# Cheeta_Driver.net
KiCad netlist of a schematic drawn in Altium Designer
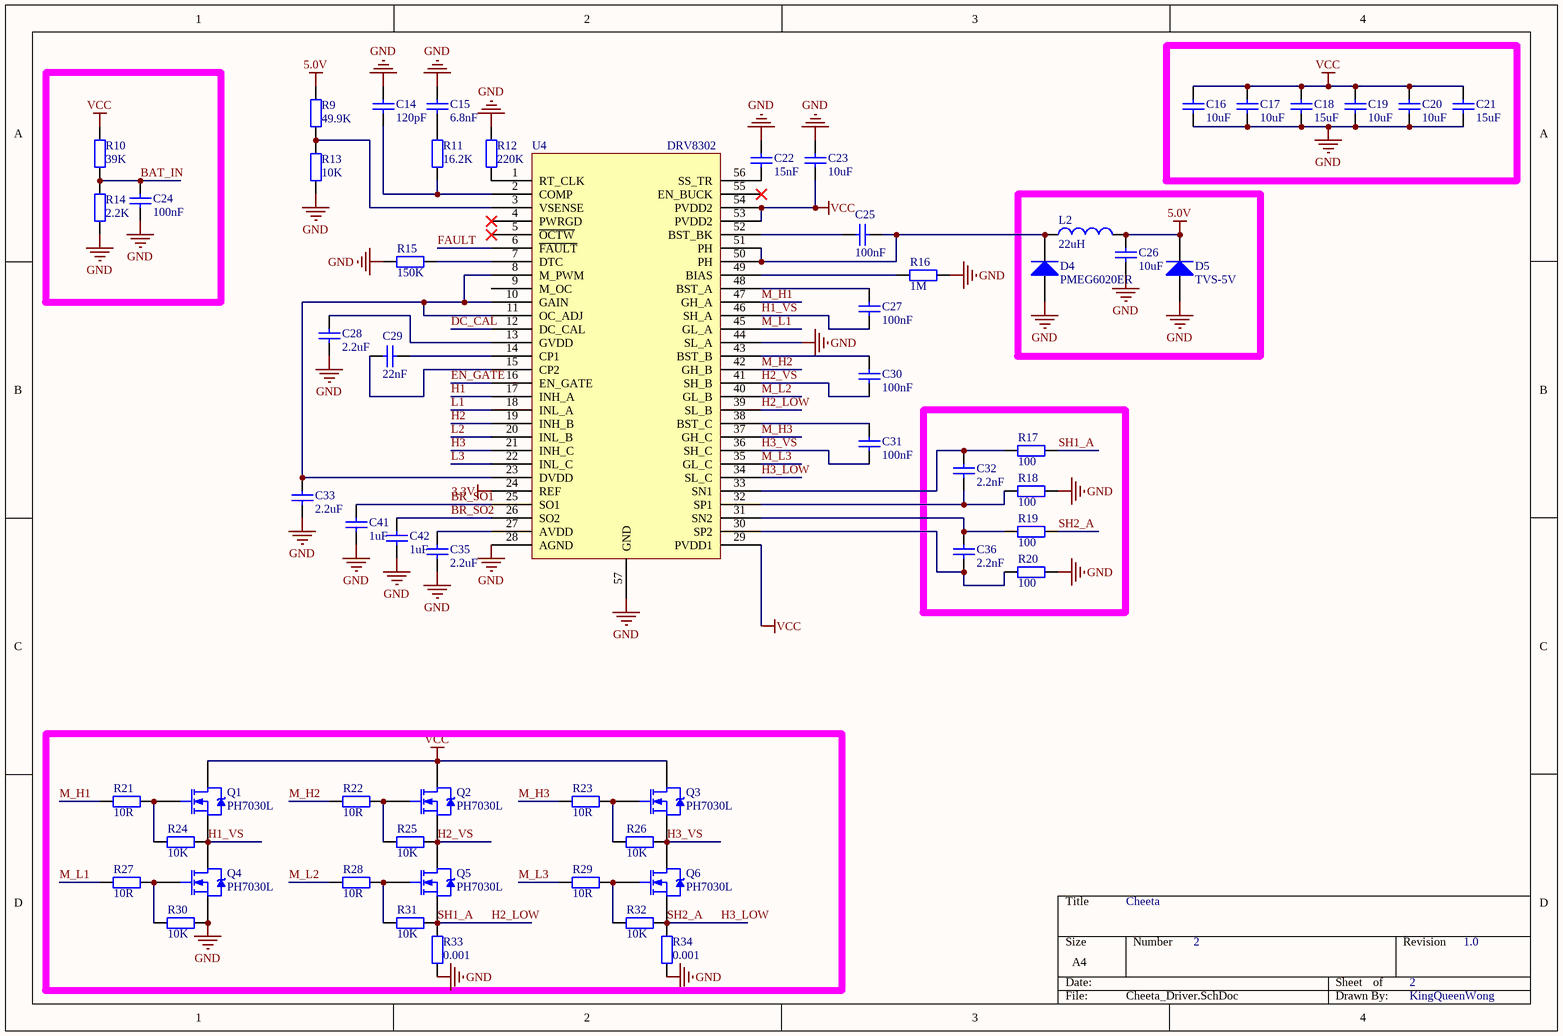
[diagram p0: Cheeta_Driver.SchDoc]

(export (version "E")
  (design (tool "Eeschema 10.0.6"))
  (components
    (comp (ref "C14")
      (value "120pF")
      (footprint "0603C")
      (description "Capacitor")
      (fields (field (name "Comment") "Cap") (field (name "PUBLISHER") "Altium Limited"))
      (libsource (lib "Miscellaneous Devices") (part "Cap"))
    )
    (comp (ref "C15")
      (value "6.8nF")
      (footprint "0603C")
      (description "Capacitor")
      (fields (field (name "Comment") "Cap") (field (name "PUBLISHER") "Altium Limited"))
      (libsource (lib "Miscellaneous Devices") (part "Cap"))
    )
    (comp (ref "C16")
      (value "10uF")
      (footprint "C1206")
      (description "Capacitor")
      (fields (field (name "Comment") "Cap") (field (name "PUBLISHER") "Altium Limited"))
      (libsource (lib "Miscellaneous Devices") (part "Cap"))
    )
    (comp (ref "C17")
      (value "10uF")
      (footprint "C1206")
      (description "Capacitor")
      (fields (field (name "Comment") "Cap") (field (name "PUBLISHER") "Altium Limited"))
      (libsource (lib "Miscellaneous Devices") (part "Cap"))
    )
    (comp (ref "C18")
      (value "15uF")
      (footprint "2220")
      (description "Capacitor")
      (fields (field (name "Comment") "Cap") (field (name "PUBLISHER") "Altium Limited"))
      (libsource (lib "Miscellaneous Devices") (part "Cap"))
    )
    (comp (ref "C19")
      (value "10uF")
      (footprint "C1206")
      (description "Capacitor")
      (fields (field (name "Comment") "Cap") (field (name "PUBLISHER") "Altium Limited"))
      (libsource (lib "Miscellaneous Devices") (part "Cap"))
    )
    (comp (ref "C20")
      (value "10uF")
      (footprint "C1206")
      (description "Capacitor")
      (fields (field (name "Comment") "Cap") (field (name "PUBLISHER") "Altium Limited"))
      (libsource (lib "Miscellaneous Devices") (part "Cap"))
    )
    (comp (ref "C21")
      (value "15uF")
      (footprint "2220")
      (description "Capacitor")
      (fields (field (name "Comment") "Cap") (field (name "PUBLISHER") "Altium Limited"))
      (libsource (lib "Miscellaneous Devices") (part "Cap"))
    )
    (comp (ref "C22")
      (value "15nF")
      (footprint "0603C")
      (description "Capacitor")
      (fields (field (name "Comment") "Cap") (field (name "PUBLISHER") "Altium Limited"))
      (libsource (lib "Miscellaneous Devices") (part "Cap"))
    )
    (comp (ref "C23")
      (value "10uF")
      (footprint "C1206")
      (description "Capacitor")
      (fields (field (name "Comment") "Cap") (field (name "PUBLISHER") "Altium Limited"))
      (libsource (lib "Miscellaneous Devices") (part "Cap"))
    )
    (comp (ref "C24")
      (value "100nF")
      (footprint "0603C")
      (description "Capacitor")
      (fields (field (name "Comment") "Cap") (field (name "PUBLISHER") "Altium Limited"))
      (libsource (lib "Miscellaneous Devices") (part "Cap"))
    )
    (comp (ref "C25")
      (value "100nF")
      (footprint "0603C")
      (description "Capacitor")
      (fields (field (name "Comment") "Cap") (field (name "PUBLISHER") "Altium Limited"))
      (libsource (lib "Miscellaneous Devices") (part "Cap"))
    )
    (comp (ref "C26")
      (value "10uF")
      (footprint "C1210")
      (description "Capacitor")
      (fields (field (name "Comment") "Cap") (field (name "PUBLISHER") "Altium Limited"))
      (libsource (lib "Miscellaneous Devices") (part "Cap"))
    )
    (comp (ref "C27")
      (value "100nF")
      (footprint "0603C")
      (description "Capacitor")
      (fields (field (name "Comment") "Cap") (field (name "PUBLISHER") "Altium Limited"))
      (libsource (lib "Miscellaneous Devices") (part "Cap"))
    )
    (comp (ref "C28")
      (value "2.2uF")
      (footprint "0603C")
      (description "Capacitor")
      (fields (field (name "Comment") "Cap") (field (name "PUBLISHER") "Altium Limited"))
      (libsource (lib "Miscellaneous Devices") (part "Cap"))
    )
    (comp (ref "C29")
      (value "22nF")
      (footprint "0603C")
      (description "Capacitor")
      (fields (field (name "Comment") "Cap") (field (name "PUBLISHER") "Altium Limited"))
      (libsource (lib "Miscellaneous Devices") (part "Cap"))
    )
    (comp (ref "C30")
      (value "100nF")
      (footprint "0603C")
      (description "Capacitor")
      (fields (field (name "Comment") "Cap") (field (name "PUBLISHER") "Altium Limited"))
      (libsource (lib "Miscellaneous Devices") (part "Cap"))
    )
    (comp (ref "C31")
      (value "100nF")
      (footprint "0603C")
      (description "Capacitor")
      (fields (field (name "Comment") "Cap") (field (name "PUBLISHER") "Altium Limited"))
      (libsource (lib "Miscellaneous Devices") (part "Cap"))
    )
    (comp (ref "C32")
      (value "2.2nF")
      (footprint "0603C")
      (description "Capacitor")
      (fields (field (name "Comment") "Cap") (field (name "PUBLISHER") "Altium Limited"))
      (libsource (lib "Miscellaneous Devices") (part "Cap"))
    )
    (comp (ref "C33")
      (value "2.2uF")
      (footprint "0603C")
      (description "Capacitor")
      (fields (field (name "Comment") "Cap") (field (name "PUBLISHER") "Altium Limited"))
      (libsource (lib "Miscellaneous Devices") (part "Cap"))
    )
    (comp (ref "C35")
      (value "2.2uF")
      (footprint "0603C")
      (description "Capacitor")
      (fields (field (name "Comment") "Cap") (field (name "PUBLISHER") "Altium Limited"))
      (libsource (lib "Miscellaneous Devices") (part "Cap"))
    )
    (comp (ref "C36")
      (value "2.2nF")
      (footprint "0603C")
      (description "Capacitor")
      (fields (field (name "Comment") "Cap") (field (name "PUBLISHER") "Altium Limited"))
      (libsource (lib "Miscellaneous Devices") (part "Cap"))
    )
    (comp (ref "C41")
      (value "1uF")
      (footprint "0603C")
      (description "Capacitor")
      (fields (field (name "Comment") "Cap") (field (name "PUBLISHER") "Altium Limited"))
      (libsource (lib "Miscellaneous Devices") (part "Cap"))
    )
    (comp (ref "C42")
      (value "1uF")
      (footprint "0603C")
      (description "Capacitor")
      (fields (field (name "Comment") "Cap") (field (name "PUBLISHER") "Altium Limited"))
      (libsource (lib "Miscellaneous Devices") (part "Cap"))
    )
    (comp (ref "D4")
      (value "PMEG6020ER")
      (footprint "SMA")
      (description "Default Diode")
      (fields (field (name "PUBLISHER") "Altium Limited"))
      (libsource (lib "Miscellaneous Devices") (part "Diode"))
    )
    (comp (ref "D5")
      (value "TVS-5V")
      (footprint "SMB")
      (description "Default Diode")
      (fields (field (name "PUBLISHER") "Altium Limited"))
      (libsource (lib "Miscellaneous Devices") (part "Diode"))
    )
    (comp (ref "L2")
      (value "22uH")
      (footprint "CD43")
      (description "Inductor")
      (fields (field (name "PUBLISHER") "Altium Limited"))
      (libsource (lib "Miscellaneous Devices") (part "Inductor"))
    )
    (comp (ref "Q1")
      (value "PH7030L")
      (footprint "SOT669")
      (description "HEXFET Power MOSFET")
      (fields (field (name "PUBLISHER") "Altium Limited"))
      (libsource (lib "Schlib") (part "PH7030L"))
    )
    (comp (ref "Q2")
      (value "PH7030L")
      (footprint "SOT669")
      (description "HEXFET Power MOSFET")
      (fields (field (name "PUBLISHER") "Altium Limited"))
      (libsource (lib "Schlib") (part "PH7030L"))
    )
    (comp (ref "Q3")
      (value "PH7030L")
      (footprint "SOT669")
      (description "HEXFET Power MOSFET")
      (fields (field (name "PUBLISHER") "Altium Limited"))
      (libsource (lib "Schlib") (part "PH7030L"))
    )
    (comp (ref "Q4")
      (value "PH7030L")
      (footprint "SOT669")
      (description "HEXFET Power MOSFET")
      (fields (field (name "PUBLISHER") "Altium Limited"))
      (libsource (lib "Schlib") (part "PH7030L"))
    )
    (comp (ref "Q5")
      (value "PH7030L")
      (footprint "SOT669")
      (description "HEXFET Power MOSFET")
      (fields (field (name "PUBLISHER") "Altium Limited"))
      (libsource (lib "Schlib") (part "PH7030L"))
    )
    (comp (ref "Q6")
      (value "PH7030L")
      (footprint "SOT669")
      (description "HEXFET Power MOSFET")
      (fields (field (name "PUBLISHER") "Altium Limited"))
      (libsource (lib "Schlib") (part "PH7030L"))
    )
    (comp (ref "R9")
      (value "49.9K")
      (footprint "0603R")
      (description "Resistor")
      (fields (field (name "Comment") "Res2") (field (name "PUBLISHER") "Altium Limited"))
      (libsource (lib "") (part "Res2_1"))
    )
    (comp (ref "R10")
      (value "39K")
      (footprint "0603R")
      (description "Resistor")
      (fields (field (name "Comment") "Res2") (field (name "PUBLISHER") "Altium Limited"))
      (libsource (lib "") (part "Res2_1"))
    )
    (comp (ref "R11")
      (value "16.2K")
      (footprint "0603R")
      (description "Resistor")
      (fields (field (name "Comment") "Res2") (field (name "PUBLISHER") "Altium Limited"))
      (libsource (lib "") (part "Res2_1"))
    )
    (comp (ref "R12")
      (value "220K")
      (footprint "0603R")
      (description "Resistor")
      (fields (field (name "Comment") "Res2") (field (name "PUBLISHER") "Altium Limited"))
      (libsource (lib "") (part "Res2_1"))
    )
    (comp (ref "R13")
      (value "10K")
      (footprint "0603R")
      (description "Resistor")
      (fields (field (name "Comment") "Res2") (field (name "PUBLISHER") "Altium Limited"))
      (libsource (lib "") (part "Res2_1"))
    )
    (comp (ref "R14")
      (value "2.2K")
      (footprint "0603R")
      (description "Resistor")
      (fields (field (name "Comment") "Res2") (field (name "PUBLISHER") "Altium Limited"))
      (libsource (lib "") (part "Res2_1"))
    )
    (comp (ref "R15")
      (value "150K")
      (footprint "0603R")
      (description "Resistor")
      (fields (field (name "Comment") "Res2") (field (name "PUBLISHER") "Altium Limited"))
      (libsource (lib "") (part "Res2_3"))
    )
    (comp (ref "R16")
      (value "1M")
      (footprint "0603R")
      (description "Resistor")
      (fields (field (name "Comment") "Res2") (field (name "PUBLISHER") "Altium Limited"))
      (libsource (lib "Miscellaneous Devices") (part "Res2"))
    )
    (comp (ref "R17")
      (value "100")
      (footprint "0603R")
      (description "Resistor")
      (fields (field (name "Comment") "Res2") (field (name "PUBLISHER") "Altium Limited"))
      (libsource (lib "Miscellaneous Devices") (part "Res2"))
    )
    (comp (ref "R18")
      (value "100")
      (footprint "0603R")
      (description "Resistor")
      (fields (field (name "Comment") "Res2") (field (name "PUBLISHER") "Altium Limited"))
      (libsource (lib "Miscellaneous Devices") (part "Res2"))
    )
    (comp (ref "R19")
      (value "100")
      (footprint "0603R")
      (description "Resistor")
      (fields (field (name "Comment") "Res2") (field (name "PUBLISHER") "Altium Limited"))
      (libsource (lib "Miscellaneous Devices") (part "Res2"))
    )
    (comp (ref "R20")
      (value "100")
      (footprint "0603R")
      (description "Resistor")
      (fields (field (name "Comment") "Res2") (field (name "PUBLISHER") "Altium Limited"))
      (libsource (lib "Miscellaneous Devices") (part "Res2"))
    )
    (comp (ref "R21")
      (value "10R")
      (footprint "0603R")
      (description "Resistor")
      (fields (field (name "Comment") "Res2") (field (name "PUBLISHER") "Altium Limited"))
      (libsource (lib "Miscellaneous Devices") (part "Res2"))
    )
    (comp (ref "R22")
      (value "10R")
      (footprint "0603R")
      (description "Resistor")
      (fields (field (name "Comment") "Res2") (field (name "PUBLISHER") "Altium Limited"))
      (libsource (lib "Miscellaneous Devices") (part "Res2"))
    )
    (comp (ref "R23")
      (value "10R")
      (footprint "0603R")
      (description "Resistor")
      (fields (field (name "Comment") "Res2") (field (name "PUBLISHER") "Altium Limited"))
      (libsource (lib "Miscellaneous Devices") (part "Res2"))
    )
    (comp (ref "R24")
      (value "10K")
      (footprint "0603R")
      (description "Resistor")
      (fields (field (name "Comment") "Res2") (field (name "PUBLISHER") "Altium Limited"))
      (libsource (lib "Miscellaneous Devices") (part "Res2"))
    )
    (comp (ref "R25")
      (value "10K")
      (footprint "0603R")
      (description "Resistor")
      (fields (field (name "Comment") "Res2") (field (name "PUBLISHER") "Altium Limited"))
      (libsource (lib "Miscellaneous Devices") (part "Res2"))
    )
    (comp (ref "R26")
      (value "10K")
      (footprint "0603R")
      (description "Resistor")
      (fields (field (name "Comment") "Res2") (field (name "PUBLISHER") "Altium Limited"))
      (libsource (lib "Miscellaneous Devices") (part "Res2"))
    )
    (comp (ref "R27")
      (value "10R")
      (footprint "0603R")
      (description "Resistor")
      (fields (field (name "Comment") "Res2") (field (name "PUBLISHER") "Altium Limited"))
      (libsource (lib "Miscellaneous Devices") (part "Res2"))
    )
    (comp (ref "R28")
      (value "10R")
      (footprint "0603R")
      (description "Resistor")
      (fields (field (name "Comment") "Res2") (field (name "PUBLISHER") "Altium Limited"))
      (libsource (lib "Miscellaneous Devices") (part "Res2"))
    )
    (comp (ref "R29")
      (value "10R")
      (footprint "0603R")
      (description "Resistor")
      (fields (field (name "Comment") "Res2") (field (name "PUBLISHER") "Altium Limited"))
      (libsource (lib "Miscellaneous Devices") (part "Res2"))
    )
    (comp (ref "R30")
      (value "10K")
      (footprint "0603R")
      (description "Resistor")
      (fields (field (name "Comment") "Res2") (field (name "PUBLISHER") "Altium Limited"))
      (libsource (lib "Miscellaneous Devices") (part "Res2"))
    )
    (comp (ref "R31")
      (value "10K")
      (footprint "0603R")
      (description "Resistor")
      (fields (field (name "Comment") "Res2") (field (name "PUBLISHER") "Altium Limited"))
      (libsource (lib "") (part "Res2_3"))
    )
    (comp (ref "R32")
      (value "10K")
      (footprint "0603R")
      (description "Resistor")
      (fields (field (name "Comment") "Res2") (field (name "PUBLISHER") "Altium Limited"))
      (libsource (lib "Miscellaneous Devices") (part "Res2"))
    )
    (comp (ref "R33")
      (value "0.001")
      (footprint "2512")
      (description "Resistor")
      (fields (field (name "Comment") "Res2") (field (name "PUBLISHER") "Altium Limited"))
      (libsource (lib "") (part "Res2_1"))
    )
    (comp (ref "R34")
      (value "0.001")
      (footprint "2512")
      (description "Resistor")
      (fields (field (name "Comment") "Res2") (field (name "PUBLISHER") "Altium Limited"))
      (libsource (lib "") (part "Res2_2"))
    )
    (comp (ref "U4") (value "DRV8302") (footprint "DGG056_L") (libsource (lib "Schlib") (part "DRV8302")))
  )
  (nets
    (net (code "1") (name "/BAT_IN") (class "Default")
      (node (ref "C24") (pin "2") (pinfunction "2_2") (pintype "passive"))
      (node (ref "R10") (pin "2") (pinfunction "2_2") (pintype "passive"))
      (node (ref "R14") (pin "1") (pinfunction "1_1") (pintype "passive"))
    )
    (net (code "2") (name "/BR_SO1") (class "Default")
      (node (ref "C41") (pin "2") (pinfunction "2_2") (pintype "passive"))
      (node (ref "U4") (pin "25") (pinfunction "SO1_25") (pintype "passive"))
    )
    (net (code "3") (name "/BR_SO2") (class "Default")
      (node (ref "C42") (pin "2") (pinfunction "2_2") (pintype "passive"))
      (node (ref "U4") (pin "26") (pinfunction "SO2_26") (pintype "passive"))
    )
    (net (code "4") (name "/DC_CAL") (class "Default")
      (node (ref "U4") (pin "12") (pinfunction "DC_CAL_12") (pintype "passive"))
    )
    (net (code "5") (name "/EN_GATE") (class "Default")
      (node (ref "U4") (pin "16") (pinfunction "EN_GATE_16") (pintype "passive"))
    )
    (net (code "6") (name "/FAULT") (class "Default")
      (node (ref "U4") (pin "6") (pinfunction "~{FAULT}_6") (pintype "passive"))
    )
    (net (code "7") (name "/H1") (class "Default")
      (node (ref "U4") (pin "17") (pinfunction "INH_A_17") (pintype "passive"))
    )
    (net (code "8") (name "/H1_VS") (class "Default")
      (node (ref "C27") (pin "2") (pinfunction "2_2") (pintype "passive"))
      (node (ref "Q1") (pin "3") (pinfunction "S_3") (pintype "passive"))
      (node (ref "Q4") (pin "2") (pinfunction "D_2") (pintype "passive"))
      (node (ref "R24") (pin "1") (pinfunction "1_1") (pintype "passive"))
      (node (ref "U4") (pin "46") (pinfunction "SH_A_46") (pintype "passive"))
    )
    (net (code "9") (name "/H2") (class "Default")
      (node (ref "U4") (pin "19") (pinfunction "INH_B_19") (pintype "passive"))
    )
    (net (code "10") (name "/H2_LOW") (class "Default")
      (node (ref "Q5") (pin "3") (pinfunction "S_3") (pintype "passive"))
      (node (ref "R17") (pin "1") (pinfunction "1_1") (pintype "passive"))
      (node (ref "R31") (pin "2") (pinfunction "2_2") (pintype "passive"))
      (node (ref "R33") (pin "1") (pinfunction "1_1") (pintype "passive"))
      (node (ref "U4") (pin "39") (pinfunction "SL_B_39") (pintype "passive"))
    )
    (net (code "11") (name "/H2_VS") (class "Default")
      (node (ref "C30") (pin "2") (pinfunction "2_2") (pintype "passive"))
      (node (ref "Q2") (pin "3") (pinfunction "S_3") (pintype "passive"))
      (node (ref "Q5") (pin "2") (pinfunction "D_2") (pintype "passive"))
      (node (ref "R25") (pin "1") (pinfunction "1_1") (pintype "passive"))
      (node (ref "U4") (pin "41") (pinfunction "SH_B_41") (pintype "passive"))
    )
    (net (code "12") (name "/H3") (class "Default")
      (node (ref "U4") (pin "21") (pinfunction "INH_C_21") (pintype "passive"))
    )
    (net (code "13") (name "/H3_LOW") (class "Default")
      (node (ref "Q6") (pin "3") (pinfunction "S_3") (pintype "passive"))
      (node (ref "R19") (pin "1") (pinfunction "1_1") (pintype "passive"))
      (node (ref "R32") (pin "1") (pinfunction "1_1") (pintype "passive"))
      (node (ref "R34") (pin "2") (pinfunction "2_2") (pintype "passive"))
      (node (ref "U4") (pin "34") (pinfunction "SL_C_34") (pintype "passive"))
    )
    (net (code "14") (name "/H3_VS") (class "Default")
      (node (ref "C31") (pin "2") (pinfunction "2_2") (pintype "passive"))
      (node (ref "Q3") (pin "3") (pinfunction "S_3") (pintype "passive"))
      (node (ref "Q6") (pin "2") (pinfunction "D_2") (pintype "passive"))
      (node (ref "R26") (pin "1") (pinfunction "1_1") (pintype "passive"))
      (node (ref "U4") (pin "36") (pinfunction "SH_C_36") (pintype "passive"))
    )
    (net (code "15") (name "/L1") (class "Default")
      (node (ref "U4") (pin "18") (pinfunction "INL_A_18") (pintype "passive"))
    )
    (net (code "16") (name "/L2") (class "Default")
      (node (ref "U4") (pin "20") (pinfunction "INL_B_20") (pintype "passive"))
    )
    (net (code "17") (name "/L3") (class "Default")
      (node (ref "U4") (pin "22") (pinfunction "INL_C_22") (pintype "passive"))
    )
    (net (code "18") (name "/M_H1") (class "Default")
      (node (ref "R21") (pin "2") (pinfunction "2_2") (pintype "passive"))
      (node (ref "U4") (pin "47") (pinfunction "GH_A_47") (pintype "passive"))
    )
    (net (code "19") (name "/M_H2") (class "Default")
      (node (ref "R22") (pin "2") (pinfunction "2_2") (pintype "passive"))
      (node (ref "U4") (pin "42") (pinfunction "GH_B_42") (pintype "passive"))
    )
    (net (code "20") (name "/M_H3") (class "Default")
      (node (ref "R23") (pin "2") (pinfunction "2_2") (pintype "passive"))
      (node (ref "U4") (pin "37") (pinfunction "GH_C_37") (pintype "passive"))
    )
    (net (code "21") (name "/M_L1") (class "Default")
      (node (ref "R27") (pin "2") (pinfunction "2_2") (pintype "passive"))
      (node (ref "U4") (pin "45") (pinfunction "GL_A_45") (pintype "passive"))
    )
    (net (code "22") (name "/M_L2") (class "Default")
      (node (ref "R28") (pin "2") (pinfunction "2_2") (pintype "passive"))
      (node (ref "U4") (pin "40") (pinfunction "GL_B_40") (pintype "passive"))
    )
    (net (code "23") (name "/M_L3") (class "Default")
      (node (ref "R29") (pin "2") (pinfunction "2_2") (pintype "passive"))
      (node (ref "U4") (pin "35") (pinfunction "GL_C_35") (pintype "passive"))
    )
    (net (code "24") (name "3.3V") (class "Default")
      (node (ref "U4") (pin "24") (pinfunction "REF_24") (pintype "passive"))
    )
    (net (code "25") (name "5.0V") (class "Default")
      (node (ref "C26") (pin "1") (pinfunction "1_1") (pintype "passive"))
      (node (ref "D5") (pin "2") (pinfunction "K_2") (pintype "passive"))
      (node (ref "L2") (pin "2") (pinfunction "2_2") (pintype "passive"))
      (node (ref "R9") (pin "1") (pinfunction "1_1") (pintype "passive"))
    )
    (net (code "26") (name "GND") (class "Default")
      (node (ref "C14") (pin "2") (pinfunction "2_2") (pintype "passive"))
      (node (ref "C15") (pin "2") (pinfunction "2_2") (pintype "passive"))
      (node (ref "C16") (pin "2") (pinfunction "2_2") (pintype "passive"))
      (node (ref "C17") (pin "2") (pinfunction "2_2") (pintype "passive"))
      (node (ref "C18") (pin "2") (pinfunction "2_2") (pintype "passive"))
      (node (ref "C19") (pin "2") (pinfunction "2_2") (pintype "passive"))
      (node (ref "C20") (pin "2") (pinfunction "2_2") (pintype "passive"))
      (node (ref "C21") (pin "2") (pinfunction "2_2") (pintype "passive"))
      (node (ref "C22") (pin "2") (pinfunction "2_2") (pintype "passive"))
      (node (ref "C23") (pin "2") (pinfunction "2_2") (pintype "passive"))
      (node (ref "C24") (pin "1") (pinfunction "1_1") (pintype "passive"))
      (node (ref "C26") (pin "2") (pinfunction "2_2") (pintype "passive"))
      (node (ref "C28") (pin "2") (pinfunction "2_2") (pintype "passive"))
      (node (ref "C33") (pin "1") (pinfunction "1_1") (pintype "passive"))
      (node (ref "C35") (pin "1") (pinfunction "1_1") (pintype "passive"))
      (node (ref "C41") (pin "1") (pinfunction "1_1") (pintype "passive"))
      (node (ref "C42") (pin "1") (pinfunction "1_1") (pintype "passive"))
      (node (ref "D4") (pin "1") (pinfunction "A_1") (pintype "passive"))
      (node (ref "D5") (pin "1") (pinfunction "A_1") (pintype "passive"))
      (node (ref "Q4") (pin "3") (pinfunction "S_3") (pintype "passive"))
      (node (ref "R12") (pin "1") (pinfunction "1_1") (pintype "passive"))
      (node (ref "R13") (pin "2") (pinfunction "2_2") (pintype "passive"))
      (node (ref "R14") (pin "2") (pinfunction "2_2") (pintype "passive"))
      (node (ref "R15") (pin "1") (pinfunction "1_1") (pintype "passive"))
      (node (ref "R16") (pin "1") (pinfunction "1_1") (pintype "passive"))
      (node (ref "R18") (pin "1") (pinfunction "1_1") (pintype "passive"))
      (node (ref "R20") (pin "1") (pinfunction "1_1") (pintype "passive"))
      (node (ref "R30") (pin "1") (pinfunction "1_1") (pintype "passive"))
      (node (ref "R33") (pin "2") (pinfunction "2_2") (pintype "passive"))
      (node (ref "R34") (pin "1") (pinfunction "1_1") (pintype "passive"))
      (node (ref "U4") (pin "28") (pinfunction "AGND_28") (pintype "passive"))
      (node (ref "U4") (pin "44") (pinfunction "SL_A_44") (pintype "passive"))
      (node (ref "U4") (pin "57") (pinfunction "GND_57") (pintype "passive"))
    )
    (net (code "27") (name "Net-(C15-Pad1)") (class "Default")
      (node (ref "C15") (pin "1") (pinfunction "1_1") (pintype "passive"))
      (node (ref "R11") (pin "1") (pinfunction "1_1") (pintype "passive"))
    )
    (net (code "28") (name "Net-(D4-K)") (class "Default")
      (node (ref "C25") (pin "2") (pinfunction "2_2") (pintype "passive"))
      (node (ref "D4") (pin "2") (pinfunction "K_2") (pintype "passive"))
      (node (ref "L2") (pin "1") (pinfunction "1_1") (pintype "passive"))
      (node (ref "U4") (pin "50") (pinfunction "PH_50") (pintype "passive"))
      (node (ref "U4") (pin "51") (pinfunction "PH_51") (pintype "passive"))
    )
    (net (code "29") (name "Net-(Q1-G)") (class "Default")
      (node (ref "Q1") (pin "1") (pinfunction "G_1") (pintype "passive"))
      (node (ref "R21") (pin "1") (pinfunction "1_1") (pintype "passive"))
      (node (ref "R24") (pin "2") (pinfunction "2_2") (pintype "passive"))
    )
    (net (code "30") (name "Net-(Q2-G)") (class "Default")
      (node (ref "Q2") (pin "1") (pinfunction "G_1") (pintype "passive"))
      (node (ref "R22") (pin "1") (pinfunction "1_1") (pintype "passive"))
      (node (ref "R25") (pin "2") (pinfunction "2_2") (pintype "passive"))
    )
    (net (code "31") (name "Net-(Q3-G)") (class "Default")
      (node (ref "Q3") (pin "1") (pinfunction "G_1") (pintype "passive"))
      (node (ref "R23") (pin "1") (pinfunction "1_1") (pintype "passive"))
      (node (ref "R26") (pin "2") (pinfunction "2_2") (pintype "passive"))
    )
    (net (code "32") (name "Net-(Q4-G)") (class "Default")
      (node (ref "Q4") (pin "1") (pinfunction "G_1") (pintype "passive"))
      (node (ref "R27") (pin "1") (pinfunction "1_1") (pintype "passive"))
      (node (ref "R30") (pin "2") (pinfunction "2_2") (pintype "passive"))
    )
    (net (code "33") (name "Net-(Q5-G)") (class "Default")
      (node (ref "Q5") (pin "1") (pinfunction "G_1") (pintype "passive"))
      (node (ref "R28") (pin "1") (pinfunction "1_1") (pintype "passive"))
      (node (ref "R31") (pin "1") (pinfunction "1_1") (pintype "passive"))
    )
    (net (code "34") (name "Net-(Q6-G)") (class "Default")
      (node (ref "Q6") (pin "1") (pinfunction "G_1") (pintype "passive"))
      (node (ref "R29") (pin "1") (pinfunction "1_1") (pintype "passive"))
      (node (ref "R32") (pin "2") (pinfunction "2_2") (pintype "passive"))
    )
    (net (code "35") (name "Net-(U4-AVDD)") (class "Default")
      (node (ref "C35") (pin "2") (pinfunction "2_2") (pintype "passive"))
      (node (ref "U4") (pin "27") (pinfunction "AVDD_27") (pintype "passive"))
    )
    (net (code "36") (name "Net-(U4-BIAS)") (class "Default")
      (node (ref "R16") (pin "2") (pinfunction "2_2") (pintype "passive"))
      (node (ref "U4") (pin "49") (pinfunction "BIAS_49") (pintype "passive"))
    )
    (net (code "37") (name "Net-(U4-BST_A)") (class "Default")
      (node (ref "C27") (pin "1") (pinfunction "1_1") (pintype "passive"))
      (node (ref "U4") (pin "48") (pinfunction "BST_A_48") (pintype "passive"))
    )
    (net (code "38") (name "Net-(U4-BST_B)") (class "Default")
      (node (ref "C30") (pin "1") (pinfunction "1_1") (pintype "passive"))
      (node (ref "U4") (pin "43") (pinfunction "BST_B_43") (pintype "passive"))
    )
    (net (code "39") (name "Net-(U4-BST_BK)") (class "Default")
      (node (ref "C25") (pin "1") (pinfunction "1_1") (pintype "passive"))
      (node (ref "U4") (pin "52") (pinfunction "BST_BK_52") (pintype "passive"))
    )
    (net (code "40") (name "Net-(U4-BST_C)") (class "Default")
      (node (ref "C31") (pin "1") (pinfunction "1_1") (pintype "passive"))
      (node (ref "U4") (pin "38") (pinfunction "BST_C_38") (pintype "passive"))
    )
    (net (code "41") (name "Net-(U4-COMP)") (class "Default")
      (node (ref "C14") (pin "1") (pinfunction "1_1") (pintype "passive"))
      (node (ref "R11") (pin "2") (pinfunction "2_2") (pintype "passive"))
      (node (ref "U4") (pin "2") (pinfunction "COMP_2") (pintype "passive"))
    )
    (net (code "42") (name "Net-(U4-CP1)") (class "Default")
      (node (ref "C29") (pin "2") (pinfunction "2_2") (pintype "passive"))
      (node (ref "U4") (pin "14") (pinfunction "CP1_14") (pintype "passive"))
    )
    (net (code "43") (name "Net-(U4-CP2)") (class "Default")
      (node (ref "C29") (pin "1") (pinfunction "1_1") (pintype "passive"))
      (node (ref "U4") (pin "15") (pinfunction "CP2_15") (pintype "passive"))
    )
    (net (code "44") (name "Net-(U4-DTC)") (class "Default")
      (node (ref "R15") (pin "2") (pinfunction "2_2") (pintype "passive"))
      (node (ref "U4") (pin "7") (pinfunction "DTC_7") (pintype "passive"))
    )
    (net (code "45") (name "Net-(U4-DVDD)") (class "Default")
      (node (ref "C33") (pin "2") (pinfunction "2_2") (pintype "passive"))
      (node (ref "U4") (pin "10") (pinfunction "GAIN_10") (pintype "passive"))
      (node (ref "U4") (pin "11") (pinfunction "OC_ADJ_11") (pintype "passive"))
      (node (ref "U4") (pin "23") (pinfunction "DVDD_23") (pintype "passive"))
      (node (ref "U4") (pin "8") (pinfunction "M_PWM_8") (pintype "passive"))
    )
    (net (code "46") (name "Net-(U4-GVDD)") (class "Default")
      (node (ref "C28") (pin "1") (pinfunction "1_1") (pintype "passive"))
      (node (ref "U4") (pin "13") (pinfunction "GVDD_13") (pintype "passive"))
    )
    (net (code "47") (name "Net-(U4-RT_CLK)") (class "Default")
      (node (ref "R12") (pin "2") (pinfunction "2_2") (pintype "passive"))
      (node (ref "U4") (pin "1") (pinfunction "RT_CLK_1") (pintype "passive"))
    )
    (net (code "48") (name "Net-(U4-SN1)") (class "Default")
      (node (ref "C32") (pin "2") (pinfunction "2_2") (pintype "passive"))
      (node (ref "R17") (pin "2") (pinfunction "2_2") (pintype "passive"))
      (node (ref "U4") (pin "33") (pinfunction "SN1_33") (pintype "passive"))
    )
    (net (code "49") (name "Net-(U4-SN2)") (class "Default")
      (node (ref "C36") (pin "2") (pinfunction "2_2") (pintype "passive"))
      (node (ref "R19") (pin "2") (pinfunction "2_2") (pintype "passive"))
      (node (ref "U4") (pin "31") (pinfunction "SN2_31") (pintype "passive"))
    )
    (net (code "50") (name "Net-(U4-SP1)") (class "Default")
      (node (ref "C32") (pin "1") (pinfunction "1_1") (pintype "passive"))
      (node (ref "R18") (pin "2") (pinfunction "2_2") (pintype "passive"))
      (node (ref "U4") (pin "32") (pinfunction "SP1_32") (pintype "passive"))
    )
    (net (code "51") (name "Net-(U4-SP2)") (class "Default")
      (node (ref "C36") (pin "1") (pinfunction "1_1") (pintype "passive"))
      (node (ref "R20") (pin "2") (pinfunction "2_2") (pintype "passive"))
      (node (ref "U4") (pin "30") (pinfunction "SP2_30") (pintype "passive"))
    )
    (net (code "52") (name "Net-(U4-SS_TR)") (class "Default")
      (node (ref "C22") (pin "1") (pinfunction "1_1") (pintype "passive"))
      (node (ref "U4") (pin "56") (pinfunction "SS_TR_56") (pintype "passive"))
    )
    (net (code "53") (name "Net-(U4-VSENSE)") (class "Default")
      (node (ref "R13") (pin "1") (pinfunction "1_1") (pintype "passive"))
      (node (ref "R9") (pin "2") (pinfunction "2_2") (pintype "passive"))
      (node (ref "U4") (pin "3") (pinfunction "VSENSE_3") (pintype "passive"))
    )
    (net (code "54") (name "VCC") (class "Default")
      (node (ref "C16") (pin "1") (pinfunction "1_1") (pintype "passive"))
      (node (ref "C17") (pin "1") (pinfunction "1_1") (pintype "passive"))
      (node (ref "C18") (pin "1") (pinfunction "1_1") (pintype "passive"))
      (node (ref "C19") (pin "1") (pinfunction "1_1") (pintype "passive"))
      (node (ref "C20") (pin "1") (pinfunction "1_1") (pintype "passive"))
      (node (ref "C21") (pin "1") (pinfunction "1_1") (pintype "passive"))
      (node (ref "C23") (pin "1") (pinfunction "1_1") (pintype "passive"))
      (node (ref "Q1") (pin "2") (pinfunction "D_2") (pintype "passive"))
      (node (ref "Q2") (pin "2") (pinfunction "D_2") (pintype "passive"))
      (node (ref "Q3") (pin "2") (pinfunction "D_2") (pintype "passive"))
      (node (ref "R10") (pin "1") (pinfunction "1_1") (pintype "passive"))
      (node (ref "U4") (pin "29") (pinfunction "PVDD1_29") (pintype "passive"))
      (node (ref "U4") (pin "53") (pinfunction "PVDD2_53") (pintype "passive"))
      (node (ref "U4") (pin "54") (pinfunction "PVDD2_54") (pintype "passive"))
    )
    (net (code "55") (name "unconnected-(U4-EN_BUCK-Pad55)") (class "Default")
      (node (ref "U4") (pin "55") (pinfunction "EN_BUCK_55") (pintype "passive+no_connect"))
    )
    (net (code "56") (name "unconnected-(U4-M_OC-Pad9)") (class "Default")
      (node (ref "U4") (pin "9") (pinfunction "M_OC_9") (pintype "passive"))
    )
    (net (code "57") (name "unconnected-(U4-PWRGD-Pad4)") (class "Default")
      (node (ref "U4") (pin "4") (pinfunction "PWRGD_4") (pintype "passive+no_connect"))
    )
    (net (code "58") (name "unconnected-(U4-~{OCTW}-Pad5)") (class "Default")
      (node (ref "U4") (pin "5") (pinfunction "~{OCTW}_5") (pintype "passive+no_connect"))
    )
  )
)
